# WX0_009_152DL.net
KiCad netlist of a schematic drawn in Altium Designer
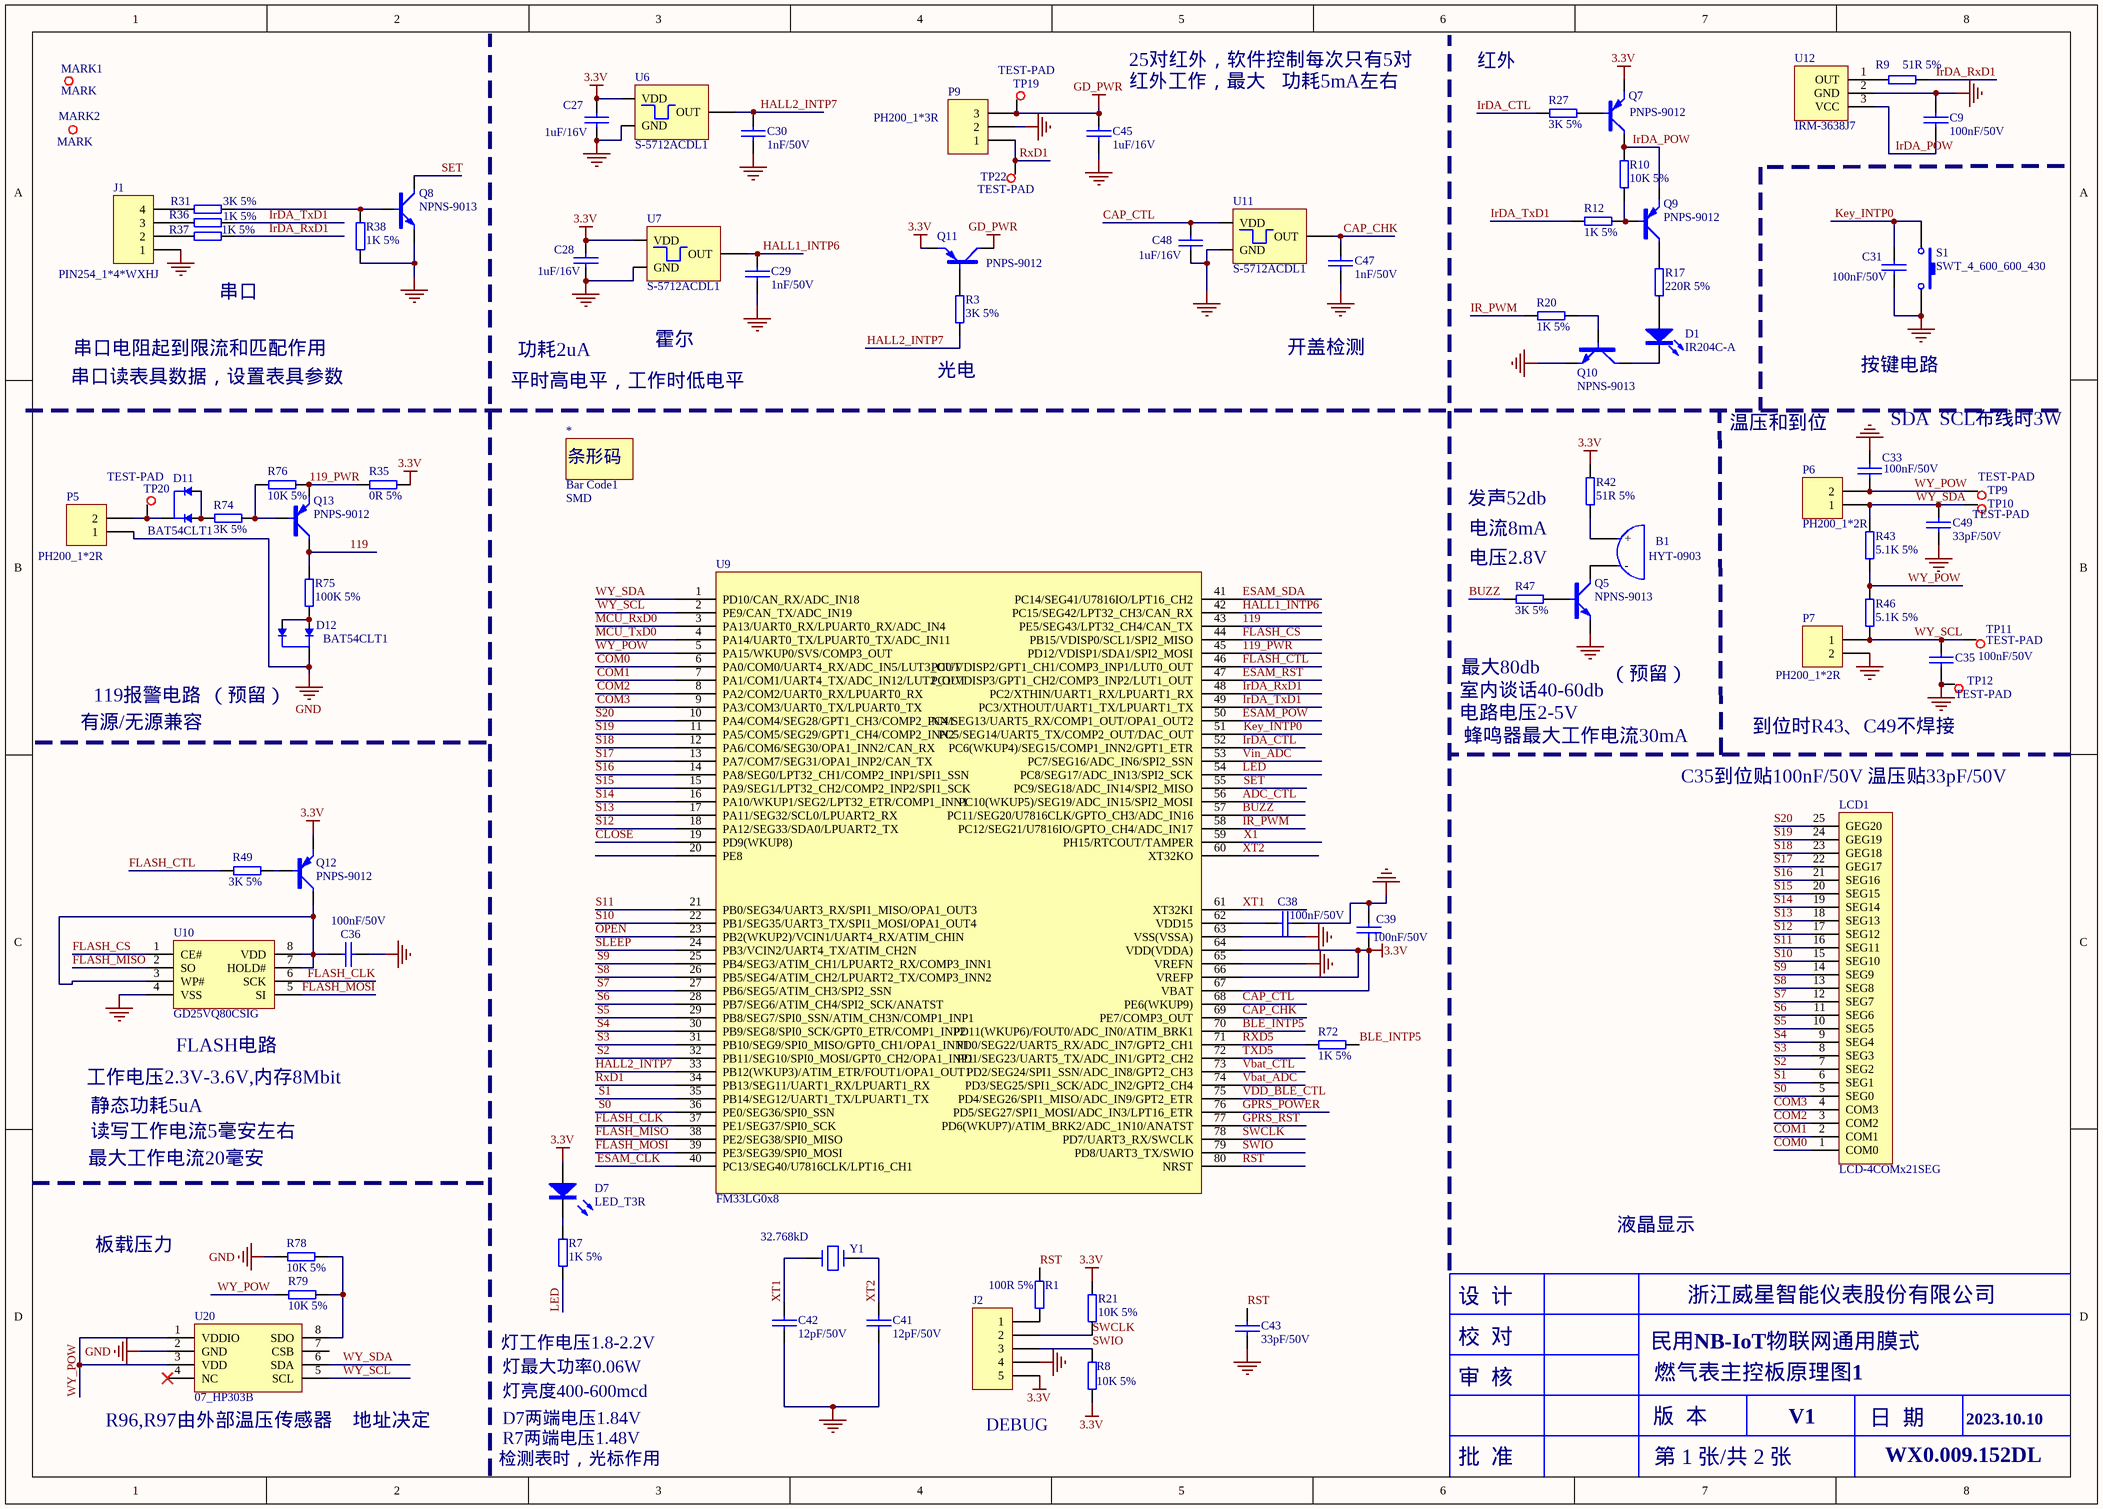
[diagram p0: WX0.009.152DL.SchDoc]

(export (version "E")
  (design (tool "Eeschema 10.0.6"))
  (components
    (comp (ref "*")
      (value "Bar Code1")
      (footprint "Bar Code1")
      (description "条形码 ,填充，无需焊接器件")
      (fields (field (name "PART NUMBER") "AD_WXHJ_Bar Code_02") (field (name "SMD/DIP") "SMD"))
      (libsource (lib "Database_Libs2") (part "05_AD_WXHJ_Bar Code_02"))
    )
    (comp (ref "B1")
      (value "HYT-0903")
      (footprint "HYT-0903")
      (description "直插,直径9mm,高5.5mm,5 V,2 V,30 mA,兴化市华宇电子有限公司,HYT-0903")
      (fields (field (name "PART NUMBER") "1010602-0007"))
      (libsource (lib "Database_Libs2") (part "07_HYT-0903"))
    )
    (comp (ref "C9")
      (value "100nF/50V")
      (footprint "CAP0603")
      (description "104pF,50 V,±10%,0603,国巨,CC0603KRX7R9BB104")
      (fields (field (name "PART NUMBER") "101020103-0021"))
      (libsource (lib "Database_Libs2") (part "CC03K7R9_100N"))
    )
    (comp (ref "C27")
      (value "1uF/16V")
      (footprint "CAP0603")
      (description "105pF,16 V,±10%,0603,国巨,CC0603KRX7R7BB105")
      (fields (field (name "PART NUMBER") "101020103-0003"))
      (libsource (lib "Database_Libs2") (part "CC03K7R7_1U"))
    )
    (comp (ref "C28")
      (value "1uF/16V")
      (footprint "CAP0603")
      (description "105pF,16 V,±10%,0603,国巨,CC0603KRX7R7BB105")
      (fields (field (name "PART NUMBER") "101020103-0003"))
      (libsource (lib "Database_Libs2") (part "CC03K7R7_1U"))
    )
    (comp (ref "C29")
      (value "1nF/50V")
      (footprint "CAP0603")
      (description "102pF,50 V,±10%,0603,国巨,CC0603KRX7R9BB102")
      (fields (field (name "PART NUMBER") "101020103-0022"))
      (libsource (lib "Database_Libs2") (part "CC03K7R9_1N"))
    )
    (comp (ref "C30")
      (value "1nF/50V")
      (footprint "CAP0603")
      (description "102pF,50 V,±10%,0603,国巨,CC0603KRX7R9BB102")
      (fields (field (name "PART NUMBER") "101020103-0022"))
      (libsource (lib "Database_Libs2") (part "CC03K7R9_1N"))
    )
    (comp (ref "C31")
      (value "100nF/50V")
      (footprint "CAP0603")
      (description "104pF,50 V,±10%,0603,国巨,CC0603KRX7R9BB104")
      (fields (field (name "PART NUMBER") "101020103-0021"))
      (libsource (lib "Database_Libs2") (part "CC03K7R9_100N"))
    )
    (comp (ref "C33")
      (value "100nF/50V")
      (footprint "CAP0603")
      (description "104pF,50 V,±10%,0603,国巨,CC0603KRX7R9BB104")
      (fields (field (name "PART NUMBER") "101020103-0021"))
      (libsource (lib "Database_Libs2") (part "CC03K7R9_100N"))
    )
    (comp (ref "C35")
      (value "100nF/50V")
      (footprint "CAP0603")
      (description "104pF,50 V,±10%,0603,国巨,CC0603KRX7R9BB104")
      (fields (field (name "PART NUMBER") "101020103-0021"))
      (libsource (lib "Database_Libs2") (part "CC03K7R9_100N"))
    )
    (comp (ref "C36")
      (value "100nF/50V")
      (footprint "CAP0603")
      (description "104pF,50 V,±10%,0603,国巨,CC0603KRX7R9BB104")
      (fields (field (name "PART NUMBER") "101020103-0021"))
      (libsource (lib "Database_Libs2") (part "CC03K7R9_100N"))
    )
    (comp (ref "C38")
      (value "100nF/50V")
      (footprint "CAP0603")
      (description "104pF,50 V,±10%,0603,国巨,CC0603KRX7R9BB104")
      (fields (field (name "PART NUMBER") "101020103-0021"))
      (libsource (lib "Database_Libs2") (part "CC03K7R9_100N"))
    )
    (comp (ref "C39")
      (value "100nF/50V")
      (footprint "CAP0603")
      (description "104pF,50 V,±10%,0603,国巨,CC0603KRX7R9BB104")
      (fields (field (name "PART NUMBER") "101020103-0021"))
      (libsource (lib "Database_Libs2") (part "CC03K7R9_100N"))
    )
    (comp (ref "C41")
      (value "12pF/50V")
      (footprint "CAP0603")
      (description "12P,50 V,±5%,0603,国巨,CC0603JRNPO9BN12")
      (fields (field (name "PART NUMBER") "101020103-0005"))
      (libsource (lib "Database_Libs2") (part "CC03JPO9_12P"))
    )
    (comp (ref "C42")
      (value "12pF/50V")
      (footprint "CAP0603")
      (description "12P,50 V,±5%,0603,国巨,CC0603JRNPO9BN12")
      (fields (field (name "PART NUMBER") "101020103-0005"))
      (libsource (lib "Database_Libs2") (part "CC03JPO9_12P"))
    )
    (comp (ref "C43")
      (value "33pF/50V")
      (footprint "CAP0603")
      (description "33pF,50 V,±10%,0603,国巨,CC0603KRNPO9BN33")
      (fields (field (name "PART NUMBER") "101020103-0027"))
      (libsource (lib "Database_Libs2") (part "CC03KPO9_33P"))
    )
    (comp (ref "C45")
      (value "1uF/16V")
      (footprint "CAP0603")
      (description "105pF,16 V,±10%,0603,国巨,CC0603KRX7R7BB105")
      (fields (field (name "PART NUMBER") "101020103-0003"))
      (libsource (lib "Database_Libs2") (part "CC03K7R7_1U"))
    )
    (comp (ref "C47")
      (value "1nF/50V")
      (footprint "CAP0603")
      (description "102pF,50 V,±10%,0603,国巨,CC0603KRX7R9BB102")
      (fields (field (name "PART NUMBER") "101020103-0022"))
      (libsource (lib "Database_Libs2") (part "CC03K7R9_1N"))
    )
    (comp (ref "C48")
      (value "1uF/16V")
      (footprint "CAP0603")
      (description "105pF,16 V,±10%,0603,国巨,CC0603KRX7R7BB105")
      (fields (field (name "PART NUMBER") "101020103-0003"))
      (libsource (lib "Database_Libs2") (part "CC03K7R7_1U"))
    )
    (comp (ref "C49")
      (value "33pF/50V")
      (footprint "CAP0603")
      (description "33pF,50 V,±10%,0603,国巨,CC0603KRNPO9BN33")
      (fields (field (name "PART NUMBER") "101020103-0027"))
      (libsource (lib "Database_Libs2") (part "CC03KPO9_33P"))
    )
    (comp (ref "D1")
      (value "IR204C-A")
      (footprint "IR_254_532_300")
      (fields (field (name "PART NUMBER") "1010502-0005"))
      (libsource (lib "Database_Libs2") (part "01_IR204C-A"))
    )
    (comp (ref "D7")
      (value "LED_T3R")
      (footprint "LED2_300")
      (description "圆形插件,3mm 圆形,插件,红光,湖北匡通电子有限公司,3BB4HC")
      (fields (field (name "PART NUMBER") "101040102-0001"))
      (libsource (lib "Database_Libs2") (part "01-LED_T3R"))
    )
    (comp (ref "D11")
      (value "BAT54CLT1")
      (footprint "SOT-23")
      (description "BAT54CLT1，SOT23-3,SOT23-3,0.2 A,0.8 V,30 V,安森美,BAT54CLT1")
      (fields (field (name "PART NUMBER") "101040101-0038"))
      (libsource (lib "Database_Libs2") (part "02_BAT54CLT1"))
    )
    (comp (ref "D12")
      (value "BAT54CLT1")
      (footprint "SOT-23")
      (description "BAT54CLT1，SOT23-3,SOT23-3,0.2 A,0.8 V,30 V,安森美,BAT54CLT1")
      (fields (field (name "PART NUMBER") "101040101-0038"))
      (libsource (lib "Database_Libs2") (part "02_BAT54CLT1"))
    )
    (comp (ref "J1")
      (value "PIN254_1*4*WXHJ")
      (footprint "PIN254_1*4*WXHJ")
      (description "1*4 ，Φ1.0 ，2.54mm，直脚,无需焊接器件")
      (fields (field (name "PART NUMBER") "AD_WXHJ_PinHeader_01"))
      (libsource (lib "Database_Libs2") (part "PIN254_1*4*WXHJ"))
    )
    (comp (ref "J2")
      (value "PIN254_1*5*WXHJ")
      (footprint "PIN254_1*5*WXHJ")
      (description "1*5 ，Φ1.0 ，2.54mm，直脚,无需焊接器件")
      (fields (field (name "PART NUMBER") "AD_WXHJ_PinHeader_02"))
      (libsource (lib "Database_Libs2") (part "PIN254_1*5*WXHJ"))
    )
    (comp (ref "LCD1")
      (value "GVH26634A-HPP")
      (footprint "PCBComponent_1")
      (description "GVH26634A-HPP-WG,65mm*23mm,针脚,段码,21,液晶,全透,70 ℃,-20 ℃,安徽金视界光电科技有限公司,GVH26634A-HPP-WG")
      (fields (field (name "PART NUMBER") "1010801-0055") (field (name "SMD/DIP") "LCD-4COMx21SEG"))
      (libsource (lib "Database_Libs2") (part "03_LCD_GVH26634A-HPP"))
    )
    (comp (ref "MARK1")
      (value "MARK")
      (footprint "MARK")
      (description "MARK点")
      (fields (field (name "PART NUMBER") "AD_WXHJ_MARK_01"))
      (libsource (lib "Database_Libs2") (part "MARK"))
    )
    (comp (ref "MARK2")
      (value "MARK")
      (footprint "MARK")
      (description "MARK点")
      (fields (field (name "PART NUMBER") "AD_WXHJ_MARK_01"))
      (libsource (lib "Database_Libs2") (part "MARK"))
    )
    (comp (ref "P5")
      (value "PH200_1*2R")
      (footprint "PH200_1*2R")
      (description "2.0-2AW,直插弯座，2PIN，脚间距2mm，带防翘起,公头,单排,2.0-2AW;直插弯座，2PIN,脚间距2mm，带防翘起")
      (fields (field (name "PART NUMBER") "1010902-0105"))
      (libsource (lib "Database_Libs2") (part "PH200_1*2R"))
    )
    (comp (ref "P6")
      (value "PH200_1*2R")
      (footprint "PCBComponent_1 - duplicate")
      (description "2.0-2AW,直插弯座，2PIN，脚间距2mm，带防翘起,公头,单排,2.0-2AW;直插弯座，2PIN,脚间距2mm，带防翘起")
      (fields (field (name "PART NUMBER") "1010902-0105"))
      (libsource (lib "Database_Libs2") (part "PH200_1*2R"))
    )
    (comp (ref "P7")
      (value "PH200_1*2R")
      (footprint "PH200_1*2R")
      (description "2.0-2AW,直插弯座，2PIN，脚间距2mm，带防翘起,公头,单排,2.0-2AW;直插弯座，2PIN,脚间距2mm，带防翘起")
      (fields (field (name "PART NUMBER") "1010902-0105"))
      (libsource (lib "") (part "PH200_1*2R_1"))
    )
    (comp (ref "P9")
      (value "PH200_1*3R")
      (footprint "PH200_1*3R")
      (description "2.0-3AW,3PIN，2mm脚间距,公头,单排,2.0-3AW；3PIN，脚间距2mm直插弯座带防翘起")
      (fields (field (name "PART NUMBER") "1010902-0104"))
      (libsource (lib "Database_Libs2") (part "PH200_1*3R"))
    )
    (comp (ref "Q5")
      (value "NPNS-9013")
      (footprint "SOT-23")
      (description "9013,NPN,SOT-23,长电,S9013")
      (fields (field (name "PART NUMBER") "101040201-0002"))
      (libsource (lib "Database_Libs2") (part "03_NPNS-9013"))
    )
    (comp (ref "Q7")
      (value "PNPS-9012")
      (footprint "SOT-23")
      (description "9012,PNP,SOT-23,JCET;长电,S9012")
      (fields (field (name "PART NUMBER") "101040201-0001"))
      (libsource (lib "Database_Libs2") (part "03_PNPS-9012"))
    )
    (comp (ref "Q8")
      (value "NPNS-9013")
      (footprint "SOT-23")
      (description "9013,NPN,SOT-23,长电,S9013")
      (fields (field (name "PART NUMBER") "101040201-0002"))
      (libsource (lib "Database_Libs2") (part "03_NPNS-9013"))
    )
    (comp (ref "Q9")
      (value "PNPS-9012")
      (footprint "SOT-23")
      (description "9012,PNP,SOT-23,JCET;长电,S9012")
      (fields (field (name "PART NUMBER") "101040201-0001"))
      (libsource (lib "Database_Libs2") (part "03_PNPS-9012"))
    )
    (comp (ref "Q10")
      (value "NPNS-9013")
      (footprint "SOT-23")
      (description "9013,NPN,SOT-23,长电,S9013")
      (fields (field (name "PART NUMBER") "101040201-0002"))
      (libsource (lib "Database_Libs2") (part "03_NPNS-9013"))
    )
    (comp (ref "Q11")
      (value "PNPS-9012")
      (footprint "SOT-23")
      (description "9012,PNP,SOT-23,JCET;长电,S9012")
      (fields (field (name "PART NUMBER") "101040201-0001"))
      (libsource (lib "Database_Libs2") (part "03_PNPS-9012"))
    )
    (comp (ref "Q12")
      (value "PNPS-9012")
      (footprint "SOT-23")
      (description "9012,PNP,SOT-23,JCET;长电,S9012")
      (fields (field (name "PART NUMBER") "101040201-0001"))
      (libsource (lib "Database_Libs2") (part "03_PNPS-9012"))
    )
    (comp (ref "Q13")
      (value "PNPS-9012")
      (footprint "SOT-23")
      (description "9012,PNP,SOT-23,JCET;长电,S9012")
      (fields (field (name "PART NUMBER") "101040201-0001"))
      (libsource (lib "Database_Libs2") (part "03_PNPS-9012"))
    )
    (comp (ref "R1")
      (value "100R 5%")
      (footprint "RES0603")
      (description "100R,±5%,1/10W,0603,国巨,RC0603JR-07100RL")
      (fields (field (name "PART NUMBER") "101010103-0022"))
      (libsource (lib "Database_Libs2") (part "RC03J_100R"))
    )
    (comp (ref "R3")
      (value "3K 5%")
      (footprint "RES0603")
      (description "国巨,±5%,0603,,155 ℃,-55 ℃,RC0603JR-073KL,无铅,100 ppm/℃,1/10W,,3K")
      (fields (field (name "PART NUMBER") "101010103-0006"))
      (libsource (lib "Database_Libs2") (part "RC03J_3K"))
    )
    (comp (ref "R7")
      (value "1K 5%")
      (footprint "RES0603")
      (description "1K,±5%,1/10W,0603,国巨,RC0603JR-071KL")
      (fields (field (name "PART NUMBER") "101010103-0008"))
      (libsource (lib "Database_Libs2") (part "RC03J_1K"))
    )
    (comp (ref "R8")
      (value "10K 5%")
      (footprint "RES0603")
      (description "国巨,±5%,0603,,155 ℃,-55 ℃,RC0603JR-0710KL,无铅,200 ppm/℃,1/10W,,10K")
      (fields (field (name "PART NUMBER") "101010103-0003"))
      (libsource (lib "Database_Libs2") (part "RC03J_10K"))
    )
    (comp (ref "R9")
      (value "51R 5%")
      (footprint "RES0603")
      (description "国巨,±5%,0603,,155 ℃,-55 ℃,RC0603JR-0751RL,无铅,100 ppm/℃,1/10W,,51欧")
      (fields (field (name "PART NUMBER") "101010103-0037"))
      (libsource (lib "Database_Libs2") (part "RC03J_51R"))
    )
    (comp (ref "R10")
      (value "10K 5%")
      (footprint "RES0603")
      (description "国巨,±5%,0603,,155 ℃,-55 ℃,RC0603JR-0710KL,无铅,200 ppm/℃,1/10W,,10K")
      (fields (field (name "PART NUMBER") "101010103-0003"))
      (libsource (lib "Database_Libs2") (part "RC03J_10K"))
    )
    (comp (ref "R12")
      (value "1K 5%")
      (footprint "RES0603")
      (description "1K,±5%,1/10W,0603,国巨,RC0603JR-071KL")
      (fields (field (name "PART NUMBER") "101010103-0008"))
      (libsource (lib "Database_Libs2") (part "RC03J_1K"))
    )
    (comp (ref "R17")
      (value "220R 5%")
      (footprint "RES0603")
      (description "220±5%,1/10W,0603,国巨,RC0603JR-07220RL")
      (fields (field (name "PART NUMBER") "101010103-0019"))
      (libsource (lib "Database_Libs2") (part "RC03J_220R"))
    )
    (comp (ref "R20")
      (value "1K 5%")
      (footprint "RES0603")
      (description "1K,±5%,1/10W,0603,国巨,RC0603JR-071KL")
      (fields (field (name "PART NUMBER") "101010103-0008"))
      (libsource (lib "Database_Libs2") (part "RC03J_1K"))
    )
    (comp (ref "R21")
      (value "10K 5%")
      (footprint "RES0603")
      (description "国巨,±5%,0603,,155 ℃,-55 ℃,RC0603JR-0710KL,无铅,200 ppm/℃,1/10W,,10K")
      (fields (field (name "PART NUMBER") "101010103-0003"))
      (libsource (lib "Database_Libs2") (part "RC03J_10K"))
    )
    (comp (ref "R27")
      (value "3K 5%")
      (footprint "RES0603")
      (description "国巨,±5%,0603,,155 ℃,-55 ℃,RC0603JR-073KL,无铅,100 ppm/℃,1/10W,,3K")
      (fields (field (name "PART NUMBER") "101010103-0006"))
      (libsource (lib "Database_Libs2") (part "RC03J_3K"))
    )
    (comp (ref "R31")
      (value "3K 5%")
      (footprint "RES0603")
      (description "国巨,±5%,0603,,155 ℃,-55 ℃,RC0603JR-073KL,无铅,100 ppm/℃,1/10W,,3K")
      (fields (field (name "PART NUMBER") "101010103-0006"))
      (libsource (lib "Database_Libs2") (part "RC03J_3K"))
    )
    (comp (ref "R35")
      (value "0R 5%")
      (footprint "RES1206")
      (description "0Ω,±5%,1/4W,1206,国巨,RC1206JR-070RL")
      (fields (field (name "PART NUMBER") "101010101-0013"))
      (libsource (lib "Database_Libs2") (part "RC06J_0R"))
    )
    (comp (ref "R36")
      (value "1K 5%")
      (footprint "RES0603")
      (description "1K,±5%,1/10W,0603,国巨,RC0603JR-071KL")
      (fields (field (name "PART NUMBER") "101010103-0008"))
      (libsource (lib "Database_Libs2") (part "RC03J_1K"))
    )
    (comp (ref "R37")
      (value "1K 5%")
      (footprint "RES0603")
      (description "1K,±5%,1/10W,0603,国巨,RC0603JR-071KL")
      (fields (field (name "PART NUMBER") "101010103-0008"))
      (libsource (lib "Database_Libs2") (part "RC03J_1K"))
    )
    (comp (ref "R38")
      (value "1K 5%")
      (footprint "RES0603")
      (description "1K,±5%,1/10W,0603,国巨,RC0603JR-071KL")
      (fields (field (name "PART NUMBER") "101010103-0008"))
      (libsource (lib "Database_Libs2") (part "RC03J_1K"))
    )
    (comp (ref "R42")
      (value "51R 5%")
      (footprint "RES0603")
      (description "国巨,±5%,0603,,155 ℃,-55 ℃,RC0603JR-0751RL,无铅,100 ppm/℃,1/10W,,51欧")
      (fields (field (name "PART NUMBER") "101010103-0037"))
      (libsource (lib "Database_Libs2") (part "RC03J_51R"))
    )
    (comp (ref "R43")
      (value "5.1K 5%")
      (footprint "RES0603")
      (description "国巨,±5%,0603,,155 ℃,55 ℃,RC0603JR-075.1KL,无铅,200 ppm/℃,1/10W,,5.1k")
      (fields (field (name "PART NUMBER") "101010103-0015"))
      (libsource (lib "Database_Libs2") (part "RC03J_5.1K"))
    )
    (comp (ref "R46")
      (value "5.1K 5%")
      (footprint "RES0603")
      (description "国巨,±5%,0603,,155 ℃,55 ℃,RC0603JR-075.1KL,无铅,200 ppm/℃,1/10W,,5.1k")
      (fields (field (name "PART NUMBER") "101010103-0015"))
      (libsource (lib "Database_Libs2") (part "RC03J_5.1K"))
    )
    (comp (ref "R47")
      (value "3K 5%")
      (footprint "RES0603")
      (description "国巨,±5%,0603,,155 ℃,-55 ℃,RC0603JR-073KL,无铅,100 ppm/℃,1/10W,,3K")
      (fields (field (name "PART NUMBER") "101010103-0006"))
      (libsource (lib "Database_Libs2") (part "RC03J_3K"))
    )
    (comp (ref "R49")
      (value "3K 5%")
      (footprint "RES0603")
      (description "国巨,±5%,0603,,155 ℃,-55 ℃,RC0603JR-073KL,无铅,100 ppm/℃,1/10W,,3K")
      (fields (field (name "PART NUMBER") "101010103-0006"))
      (libsource (lib "Database_Libs2") (part "RC03J_3K"))
    )
    (comp (ref "R72")
      (value "1K 5%")
      (footprint "RES0603")
      (description "1K,±5%,1/10W,0603,国巨,RC0603JR-071KL")
      (fields (field (name "PART NUMBER") "101010103-0008"))
      (libsource (lib "Database_Libs2") (part "RC03J_1K"))
    )
    (comp (ref "R74")
      (value "3K 5%")
      (footprint "RES0603")
      (description "国巨,±5%,0603,,155 ℃,-55 ℃,RC0603JR-073KL,无铅,100 ppm/℃,1/10W,,3K")
      (fields (field (name "PART NUMBER") "101010103-0006"))
      (libsource (lib "Database_Libs2") (part "RC03J_3K"))
    )
    (comp (ref "R75")
      (value "100K 5%")
      (footprint "RES0603")
      (description "国巨,±5%,0603,,155 ℃,-55 ℃,RC0603JR-07100KL,无铅,100 ppm/℃,1/10W,,100K")
      (fields (field (name "PART NUMBER") "101010103-0005"))
      (libsource (lib "Database_Libs2") (part "RC03J_100K"))
    )
    (comp (ref "R76")
      (value "10K 5%")
      (footprint "RES0603")
      (description "国巨,±5%,0603,,155 ℃,-55 ℃,RC0603JR-0710KL,无铅,200 ppm/℃,1/10W,,10K")
      (fields (field (name "PART NUMBER") "101010103-0003"))
      (libsource (lib "Database_Libs2") (part "RC03J_10K"))
    )
    (comp (ref "R78")
      (value "10K 5%")
      (footprint "RES0603")
      (description "国巨,±5%,0603,,155 ℃,-55 ℃,RC0603JR-071ML,无铅,200 ppm/℃,1/10W,,1M")
      (fields (field (name "PART NUMBER") "101010103-0002"))
      (libsource (lib "Database_Libs2") (part "RC03J_1M"))
    )
    (comp (ref "R79")
      (value "10K 5%")
      (footprint "RES0603")
      (description "国巨,±5%,0603,,155 ℃,-55 ℃,RC0603JR-071ML,无铅,200 ppm/℃,1/10W,,1M")
      (fields (field (name "PART NUMBER") "101010103-0002"))
      (libsource (lib "Database_Libs2") (part "RC03J_1M"))
    )
    (comp (ref "S1")
      (value "SWT_4_600_600_430")
      (footprint "SWT_4_600_600")
      (description "TS-1102,机械轻触,6*6*4.3直插,6*6*4.3直插,乐清市羽欧电子")
      (fields (field (name "PART NUMBER") "1011001-0027"))
      (libsource (lib "Database_Libs2") (part "07_SWT_4_600_600_430"))
    )
    (comp (ref "TP9")
      (value "TEST-PAD")
      (footprint "TEST-PAD")
      (description "单面焊盘测试点")
      (fields (field (name "PART NUMBER") "AD_WXHJ_TEST-PAD_01"))
      (libsource (lib "Database_Libs2") (part "TEST-PAD"))
    )
    (comp (ref "TP10")
      (value "TEST-PAD")
      (footprint "TEST-PAD")
      (description "单面焊盘测试点")
      (fields (field (name "PART NUMBER") "AD_WXHJ_TEST-PAD_01"))
      (libsource (lib "Database_Libs2") (part "TEST-PAD"))
    )
    (comp (ref "TP11")
      (value "TEST-PAD")
      (footprint "TEST-PAD")
      (description "单面焊盘测试点")
      (fields (field (name "PART NUMBER") "AD_WXHJ_TEST-PAD_01"))
      (libsource (lib "Database_Libs2") (part "TEST-PAD"))
    )
    (comp (ref "TP12")
      (value "TEST-PAD")
      (footprint "TEST-PAD")
      (description "单面焊盘测试点")
      (fields (field (name "PART NUMBER") "AD_WXHJ_TEST-PAD_01"))
      (libsource (lib "Database_Libs2") (part "TEST-PAD"))
    )
    (comp (ref "TP19")
      (value "TEST-PAD")
      (footprint "TEST-PAD")
      (description "单面焊盘测试点")
      (fields (field (name "PART NUMBER") "AD_WXHJ_TEST-PAD_01"))
      (libsource (lib "Database_Libs2") (part "TEST-PAD"))
    )
    (comp (ref "TP20")
      (value "TEST-PAD")
      (footprint "TEST-PAD")
      (description "单面焊盘测试点")
      (fields (field (name "PART NUMBER") "AD_WXHJ_TEST-PAD_01"))
      (libsource (lib "Database_Libs2") (part "TEST-PAD"))
    )
    (comp (ref "TP22")
      (value "TEST-PAD")
      (footprint "TEST-PAD")
      (description "单面焊盘测试点")
      (fields (field (name "PART NUMBER") "AD_WXHJ_TEST-PAD_01"))
      (libsource (lib "Database_Libs2") (part "TEST-PAD"))
    )
    (comp (ref "U6")
      (value "S-5712ACDL1")
      (footprint "SOT-23")
      (description "S-5712ACDL1,SOT23-3,3.5 V,1.6 V,2 uA,精工电子,S-5712ACDL1")
      (fields (field (name "PART NUMBER") "1010504-0002"))
      (libsource (lib "Database_Libs2") (part "01_S-5712ACDL1"))
    )
    (comp (ref "U7")
      (value "S-5712ACDL1")
      (footprint "SOT-23")
      (description "S-5712ACDL1,SOT23-3,3.5 V,1.6 V,2 uA,精工电子,S-5712ACDL1")
      (fields (field (name "PART NUMBER") "1010504-0002"))
      (libsource (lib "Database_Libs2") (part "01_S-5712ACDL1"))
    )
    (comp (ref "U9") (value "FM33LG0x8") (footprint "LQFP80") (libsource (lib "FM_MCU") (part "FM33LG0x8")))
    (comp (ref "U10")
      (value "GD25VQ80CSIG")
      (footprint "SOP-8L-200MIL")
      (description "GD25VQ80CSIG,SOP8 208mil,北京兆易创新科技股份有限公司,GD25VQ80CSIG")
      (fields (field (name "PART NUMBER") "101050101-0165"))
      (libsource (lib "Database_Libs2") (part "04_GD25VQ80CSIG"))
    )
    (comp (ref "U11")
      (value "S-5712ACDL1")
      (footprint "SOT-23")
      (description "S-5712ACDL1,SOT23-3,3.5 V,1.6 V,2 uA,精工电子,S-5712ACDL1")
      (fields (field (name "PART NUMBER") "1010504-0002"))
      (libsource (lib "Database_Libs2") (part "01_S-5712ACDL1"))
    )
    (comp (ref "U12")
      (value "IRM-3638J7")
      (footprint "IRM-3638J7")
      (description "IRM-3638J7  直脚,插件,6 V,6 V,亿光电子工业股份有限公司,IRM-3638J7")
      (fields (field (name "PART NUMBER") "101040101-0059"))
      (libsource (lib "Database_Libs2") (part "01_IRM-3638J7"))
    )
    (comp (ref "U20")
      (value "07_HP303B")
      (footprint "HP303B")
      (description "HP303B,4.7mm*3.7mm,惠贻华普,HP303B,含铅")
      (fields (field (name "PART NUMBER") "1011301-0022"))
      (libsource (lib "Database_Libs2") (part "07_HP303B"))
    )
    (comp (ref "Y1")
      (value "32.768kD")
      (footprint "SMD-3215_2P")
      (fields (field (name "PART NUMBER") "1010601-0020"))
      (libsource (lib "Database_Libs2") (part "04_XTALSG12MD_32.768kD"))
    )
  )
  (nets
    (net (code "1") (name "/119") (class "Default")
      (node (ref "Q13") (pin "3") (pinfunction "C_3") (pintype "passive"))
      (node (ref "R75") (pin "2") (pinfunction "2_2") (pintype "passive"))
      (node (ref "U9") (pin "43") (pinfunction "PE5/SEG43/LPT32_CH4/CAN_TX_43") (pintype "passive"))
    )
    (net (code "2") (name "/119_PWR") (class "Default")
      (node (ref "Q13") (pin "2") (pinfunction "E_2") (pintype "passive"))
      (node (ref "R35") (pin "2") (pinfunction "2_2") (pintype "passive"))
      (node (ref "R76") (pin "1") (pinfunction "1_1") (pintype "passive"))
      (node (ref "U9") (pin "45") (pinfunction "PD12/VDISP1/SDA1/SPI2_MOSI_45") (pintype "passive"))
    )
    (net (code "3") (name "/ADC_CTL") (class "Default")
      (node (ref "U9") (pin "56") (pinfunction "PC10(WKUP5)/SEG19/ADC_IN15/SPI2_MOSI_56") (pintype "passive"))
    )
    (net (code "4") (name "/BLE_INTP5") (class "Default")
      (node (ref "R72") (pin "1") (pinfunction "1_1") (pintype "passive"))
      (node (ref "U9") (pin "70") (pinfunction "PD11(WKUP6)/FOUT0/ADC_IN0/ATIM_BRK1_70") (pintype "passive"))
    )
    (net (code "5") (name "/BUZZ") (class "Default")
      (node (ref "R47") (pin "1") (pinfunction "1_1") (pintype "passive"))
      (node (ref "U9") (pin "57") (pinfunction "PC11/SEG20/U7816CLK/GPTO_CH3/ADC_IN16_57") (pintype "passive"))
    )
    (net (code "6") (name "/CAP_CHK") (class "Default")
      (node (ref "C47") (pin "1") (pinfunction "1_1") (pintype "passive"))
      (node (ref "U11") (pin "2") (pinfunction "OUT_2") (pintype "passive"))
      (node (ref "U9") (pin "69") (pinfunction "PE7/COMP3_OUT_69") (pintype "passive"))
    )
    (net (code "7") (name "/CAP_CTL") (class "Default")
      (node (ref "C48") (pin "1") (pinfunction "1_1") (pintype "passive"))
      (node (ref "U11") (pin "1") (pinfunction "VDD_1") (pintype "passive"))
      (node (ref "U9") (pin "68") (pinfunction "PE6(WKUP9)_68") (pintype "passive"))
    )
    (net (code "8") (name "/CLOSE") (class "Default")
      (node (ref "U9") (pin "19") (pinfunction "PD9(WKUP8)_19") (pintype "passive"))
    )
    (net (code "9") (name "/COM0") (class "Default")
      (node (ref "LCD1") (pin "1") (pinfunction "COM0_1") (pintype "passive"))
      (node (ref "U9") (pin "6") (pinfunction "PA0/COM0/UART4_RX/ADC_IN5/LUT3_OUT_6") (pintype "passive"))
    )
    (net (code "10") (name "/COM1") (class "Default")
      (node (ref "LCD1") (pin "2") (pinfunction "COM1_2") (pintype "passive"))
      (node (ref "U9") (pin "7") (pinfunction "PA1/COM1/UART4_TX/ADC_IN12/LUT2_OUT_7") (pintype "passive"))
    )
    (net (code "11") (name "/COM2") (class "Default")
      (node (ref "LCD1") (pin "3") (pinfunction "COM2_3") (pintype "passive"))
      (node (ref "U9") (pin "8") (pinfunction "PA2/COM2/UART0_RX/LPUART0_RX_8") (pintype "passive"))
    )
    (net (code "12") (name "/COM3") (class "Default")
      (node (ref "LCD1") (pin "4") (pinfunction "COM3_4") (pintype "passive"))
      (node (ref "U9") (pin "9") (pinfunction "PA3/COM3/UART0_TX/LPUART0_TX_9") (pintype "passive"))
    )
    (net (code "13") (name "/ESAM_CLK") (class "Default")
      (node (ref "U9") (pin "40") (pinfunction "PC13/SEG40/U7816CLK/LPT16_CH1_40") (pintype "passive"))
    )
    (net (code "14") (name "/ESAM_POW") (class "Default")
      (node (ref "U9") (pin "50") (pinfunction "PC4/SEG13/UART5_RX/COMP1_OUT/OPA1_OUT2_50") (pintype "passive"))
    )
    (net (code "15") (name "/ESAM_RST") (class "Default")
      (node (ref "U9") (pin "47") (pinfunction "PC1/VDISP3/GPT1_CH2/COMP3_INP2/LUT1_OUT_47") (pintype "passive"))
    )
    (net (code "16") (name "/ESAM_SDA") (class "Default")
      (node (ref "U9") (pin "41") (pinfunction "PC14/SEG41/U7816IO/LPT16_CH2_41") (pintype "passive"))
    )
    (net (code "17") (name "/FLASH_CLK") (class "Default")
      (node (ref "U10") (pin "6") (pinfunction "SCK_6") (pintype "passive"))
      (node (ref "U9") (pin "37") (pinfunction "PE1/SEG37/SPI0_SCK_37") (pintype "passive"))
    )
    (net (code "18") (name "/FLASH_CS") (class "Default")
      (node (ref "U10") (pin "1") (pinfunction "CE#_1") (pintype "passive"))
      (node (ref "U9") (pin "44") (pinfunction "PB15/VDISP0/SCL1/SPI2_MISO_44") (pintype "passive"))
    )
    (net (code "19") (name "/FLASH_CTL") (class "Default")
      (node (ref "R49") (pin "1") (pinfunction "1_1") (pintype "passive"))
      (node (ref "U9") (pin "46") (pinfunction "PC0/VDISP2/GPT1_CH1/COMP3_INP1/LUT0_OUT_46") (pintype "passive"))
    )
    (net (code "20") (name "/FLASH_MISO") (class "Default")
      (node (ref "U10") (pin "2") (pinfunction "SO_2") (pintype "passive"))
      (node (ref "U9") (pin "38") (pinfunction "PE2/SEG38/SPI0_MISO_38") (pintype "passive"))
    )
    (net (code "21") (name "/FLASH_MOSI") (class "Default")
      (node (ref "U10") (pin "5") (pinfunction "SI_5") (pintype "passive"))
      (node (ref "U9") (pin "39") (pinfunction "PE3/SEG39/SPI0_MOSI_39") (pintype "passive"))
    )
    (net (code "22") (name "/GPRS_POWER") (class "Default")
      (node (ref "U9") (pin "76") (pinfunction "PD5/SEG27/SPI1_MOSI/ADC_IN3/LPT16_ETR_76") (pintype "passive"))
    )
    (net (code "23") (name "/GPRS_RST") (class "Default")
      (node (ref "U9") (pin "77") (pinfunction "PD6(WKUP7)/ATIM_BRK2/ADC_1N10/ANATST_77") (pintype "passive"))
    )
    (net (code "24") (name "/HALL1_INTP6") (class "Default")
      (node (ref "C29") (pin "1") (pinfunction "1_1") (pintype "passive"))
      (node (ref "U7") (pin "2") (pinfunction "OUT_2") (pintype "passive"))
      (node (ref "U9") (pin "42") (pinfunction "PC15/SEG42/LPT32_CH3/CAN_RX_42") (pintype "passive"))
    )
    (net (code "25") (name "/HALL2_INTP7") (class "Default")
      (node (ref "C30") (pin "1") (pinfunction "1_1") (pintype "passive"))
      (node (ref "R3") (pin "1") (pinfunction "1_1") (pintype "passive"))
      (node (ref "U6") (pin "2") (pinfunction "OUT_2") (pintype "passive"))
      (node (ref "U9") (pin "33") (pinfunction "PB12(WKUP3)/ATIM_ETR/FOUT1/OPA1_OUT1_33") (pintype "passive"))
    )
    (net (code "26") (name "/IR_PWM") (class "Default")
      (node (ref "R20") (pin "1") (pinfunction "1_1") (pintype "passive"))
      (node (ref "U9") (pin "58") (pinfunction "PC12/SEG21/U7816IO/GPTO_CH4/ADC_IN17_58") (pintype "passive"))
    )
    (net (code "27") (name "/IrDA_CTL") (class "Default")
      (node (ref "R27") (pin "1") (pinfunction "1_1") (pintype "passive"))
      (node (ref "U9") (pin "52") (pinfunction "PC6(WKUP4)/SEG15/COMP1_INN2/GPT1_ETR_52") (pintype "passive"))
    )
    (net (code "28") (name "/IrDA_POW") (class "Default")
      (node (ref "C9") (pin "2") (pinfunction "2_2") (pintype "passive"))
      (node (ref "Q7") (pin "3") (pinfunction "C_3") (pintype "passive"))
      (node (ref "Q9") (pin "2") (pinfunction "E_2") (pintype "passive"))
      (node (ref "R10") (pin "2") (pinfunction "2_2") (pintype "passive"))
      (node (ref "U12") (pin "3") (pinfunction "VCC_3") (pintype "passive"))
    )
    (net (code "29") (name "/IrDA_RxD1") (class "Default")
      (node (ref "R37") (pin "2") (pinfunction "2_2") (pintype "passive"))
      (node (ref "R9") (pin "2") (pinfunction "2_2") (pintype "passive"))
      (node (ref "U9") (pin "48") (pinfunction "PC2/XTHIN/UART1_RX/LPUART1_RX_48") (pintype "passive"))
    )
    (net (code "30") (name "/IrDA_TxD1") (class "Default")
      (node (ref "R12") (pin "1") (pinfunction "1_1") (pintype "passive"))
      (node (ref "R36") (pin "2") (pinfunction "2_2") (pintype "passive"))
      (node (ref "U9") (pin "49") (pinfunction "PC3/XTHOUT/UART1_TX/LPUART1_TX_49") (pintype "passive"))
    )
    (net (code "31") (name "/Key_INTP0") (class "Default")
      (node (ref "C31") (pin "1") (pinfunction "1_1") (pintype "passive"))
      (node (ref "S1") (pin "1") (pinfunction "1_1") (pintype "passive"))
      (node (ref "U9") (pin "51") (pinfunction "PC5/SEG14/UART5_TX/COMP2_OUT/DAC_OUT_51") (pintype "passive"))
    )
    (net (code "32") (name "/LED") (class "Default")
      (node (ref "R7") (pin "1") (pinfunction "1_1") (pintype "passive"))
      (node (ref "U9") (pin "54") (pinfunction "PC8/SEG17/ADC_IN13/SPI2_SCK_54") (pintype "passive"))
    )
    (net (code "33") (name "/MCU_RxD0") (class "Default")
      (node (ref "U9") (pin "3") (pinfunction "PA13/UART0_RX/LPUART0_RX/ADC_IN4_3") (pintype "passive"))
    )
    (net (code "34") (name "/MCU_TxD0") (class "Default")
      (node (ref "U9") (pin "4") (pinfunction "PA14/UART0_TX/LPUART0_TX/ADC_IN11_4") (pintype "passive"))
    )
    (net (code "35") (name "/OPEN") (class "Default")
      (node (ref "U9") (pin "23") (pinfunction "PB2(WKUP2)/VCIN1/UART4_RX/ATIM_CHIN_23") (pintype "passive"))
    )
    (net (code "36") (name "/RST") (class "Default")
      (node (ref "C43") (pin "1") (pinfunction "1_1") (pintype "passive"))
      (node (ref "R1") (pin "1") (pinfunction "1_1") (pintype "passive"))
      (node (ref "U9") (pin "80") (pinfunction "NRST_80") (pintype "passive"))
    )
    (net (code "37") (name "/RXD5") (class "Default")
      (node (ref "R72") (pin "2") (pinfunction "2_2") (pintype "passive"))
      (node (ref "U9") (pin "71") (pinfunction "PD0/SEG22/UART5_RX/ADC_IN7/GPT2_CH1_71") (pintype "passive"))
    )
    (net (code "38") (name "/RxD1") (class "Default")
      (node (ref "P9") (pin "1") (pinfunction "1_1") (pintype "passive"))
      (node (ref "TP22") (pin "1") (pinfunction "1_1") (pintype "passive"))
      (node (ref "U9") (pin "34") (pinfunction "PB13/SEG11/UART1_RX/LPUART1_RX_34") (pintype "passive"))
    )
    (net (code "39") (name "/S0") (class "Default")
      (node (ref "LCD1") (pin "5") (pinfunction "SEG0_5") (pintype "passive"))
      (node (ref "U9") (pin "36") (pinfunction "PE0/SEG36/SPI0_SSN_36") (pintype "passive"))
    )
    (net (code "40") (name "/S1") (class "Default")
      (node (ref "LCD1") (pin "6") (pinfunction "SEG1_6") (pintype "passive"))
      (node (ref "U9") (pin "35") (pinfunction "PB14/SEG12/UART1_TX/LPUART1_TX_35") (pintype "passive"))
    )
    (net (code "41") (name "/S2") (class "Default")
      (node (ref "LCD1") (pin "7") (pinfunction "SEG2_7") (pintype "passive"))
      (node (ref "U9") (pin "32") (pinfunction "PB11/SEG10/SPI0_MOSI/GPT0_CH2/OPA1_INP1_32") (pintype "passive"))
    )
    (net (code "42") (name "/S3") (class "Default")
      (node (ref "LCD1") (pin "8") (pinfunction "SEG3_8") (pintype "passive"))
      (node (ref "U9") (pin "31") (pinfunction "PB10/SEG9/SPI0_MISO/GPT0_CH1/OPA1_INN1_31") (pintype "passive"))
    )
    (net (code "43") (name "/S4") (class "Default")
      (node (ref "LCD1") (pin "9") (pinfunction "SEG4_9") (pintype "passive"))
      (node (ref "U9") (pin "30") (pinfunction "PB9/SEG8/SPI0_SCK/GPT0_ETR/COMP1_INP2_30") (pintype "passive"))
    )
    (net (code "44") (name "/S5") (class "Default")
      (node (ref "LCD1") (pin "10") (pinfunction "SEG5_10") (pintype "passive"))
      (node (ref "U9") (pin "29") (pinfunction "PB8/SEG7/SPI0_SSN/ATIM_CH3N/COMP1_INP1_29") (pintype "passive"))
    )
    (net (code "45") (name "/S6") (class "Default")
      (node (ref "LCD1") (pin "11") (pinfunction "SEG6_11") (pintype "passive"))
      (node (ref "U9") (pin "28") (pinfunction "PB7/SEG6/ATIM_CH4/SPI2_SCK/ANATST_28") (pintype "passive"))
    )
    (net (code "46") (name "/S7") (class "Default")
      (node (ref "LCD1") (pin "12") (pinfunction "SEG7_12") (pintype "passive"))
      (node (ref "U9") (pin "27") (pinfunction "PB6/SEG5/ATIM_CH3/SPI2_SSN_27") (pintype "passive"))
    )
    (net (code "47") (name "/S8") (class "Default")
      (node (ref "LCD1") (pin "13") (pinfunction "SEG8_13") (pintype "passive"))
      (node (ref "U9") (pin "26") (pinfunction "PB5/SEG4/ATIM_CH2/LPUART2_TX/COMP3_INN2_26") (pintype "passive"))
    )
    (net (code "48") (name "/S9") (class "Default")
      (node (ref "LCD1") (pin "14") (pinfunction "SEG9_14") (pintype "passive"))
      (node (ref "U9") (pin "25") (pinfunction "PB4/SEG3/ATIM_CH1/LPUART2_RX/COMP3_INN1_25") (pintype "passive"))
    )
    (net (code "49") (name "/S10") (class "Default")
      (node (ref "LCD1") (pin "15") (pinfunction "SEG10_15") (pintype "passive"))
      (node (ref "U9") (pin "22") (pinfunction "PB1/SEG35/UART3_TX/SPI1_MOSI/OPA1_OUT4_22") (pintype "passive"))
    )
    (net (code "50") (name "/S11") (class "Default")
      (node (ref "LCD1") (pin "16") (pinfunction "SEG11_16") (pintype "passive"))
      (node (ref "U9") (pin "21") (pinfunction "PB0/SEG34/UART3_RX/SPI1_MISO/OPA1_OUT3_21") (pintype "passive"))
    )
    (net (code "51") (name "/S12") (class "Default")
      (node (ref "LCD1") (pin "17") (pinfunction "SEG12_17") (pintype "passive"))
      (node (ref "U9") (pin "18") (pinfunction "PA12/SEG33/SDA0/LPUART2_TX_18") (pintype "passive"))
    )
    (net (code "52") (name "/S13") (class "Default")
      (node (ref "LCD1") (pin "18") (pinfunction "SEG13_18") (pintype "passive"))
      (node (ref "U9") (pin "17") (pinfunction "PA11/SEG32/SCL0/LPUART2_RX_17") (pintype "passive"))
    )
    (net (code "53") (name "/S14") (class "Default")
      (node (ref "LCD1") (pin "19") (pinfunction "SEG14_19") (pintype "passive"))
      (node (ref "U9") (pin "16") (pinfunction "PA10/WKUP1/SEG2/LPT32_ETR/COMP1_INN1_16") (pintype "passive"))
    )
    (net (code "54") (name "/S15") (class "Default")
      (node (ref "LCD1") (pin "20") (pinfunction "SEG15_20") (pintype "passive"))
      (node (ref "U9") (pin "15") (pinfunction "PA9/SEG1/LPT32_CH2/COMP2_INP2/SPI1_SCK_15") (pintype "passive"))
    )
    (net (code "55") (name "/S16") (class "Default")
      (node (ref "LCD1") (pin "21") (pinfunction "SEG16_21") (pintype "passive"))
      (node (ref "U9") (pin "14") (pinfunction "PA8/SEG0/LPT32_CH1/COMP2_INP1/SPI1_SSN_14") (pintype "passive"))
    )
    (net (code "56") (name "/S17") (class "Default")
      (node (ref "LCD1") (pin "22") (pinfunction "GEG17_22") (pintype "passive"))
      (node (ref "U9") (pin "13") (pinfunction "PA7/COM7/SEG31/OPA1_INP2/CAN_TX_13") (pintype "passive"))
    )
    (net (code "57") (name "/S18") (class "Default")
      (node (ref "LCD1") (pin "23") (pinfunction "GEG18_23") (pintype "passive"))
      (node (ref "U9") (pin "12") (pinfunction "PA6/COM6/SEG30/OPA1_INN2/CAN_RX_12") (pintype "passive"))
    )
    (net (code "58") (name "/S19") (class "Default")
      (node (ref "LCD1") (pin "24") (pinfunction "GEG19_24") (pintype "passive"))
      (node (ref "U9") (pin "11") (pinfunction "PA5/COM5/SEG29/GPT1_CH4/COMP2_INN2_11") (pintype "passive"))
    )
    (net (code "59") (name "/S20") (class "Default")
      (node (ref "LCD1") (pin "25") (pinfunction "GEG20_25") (pintype "passive"))
      (node (ref "U9") (pin "10") (pinfunction "PA4/COM4/SEG28/GPT1_CH3/COMP2_INN1_10") (pintype "passive"))
    )
    (net (code "60") (name "/SET") (class "Default")
      (node (ref "Q8") (pin "3") (pinfunction "C_3") (pintype "passive"))
      (node (ref "U9") (pin "55") (pinfunction "PC9/SEG18/ADC_IN14/SPI2_MISO_55") (pintype "passive"))
    )
    (net (code "61") (name "/SLEEP") (class "Default")
      (node (ref "U9") (pin "24") (pinfunction "PB3/VCIN2/UART4_TX/ATIM_CH2N_24") (pintype "passive"))
    )
    (net (code "62") (name "/SWCLK") (class "Default")
      (node (ref "J2") (pin "2") (pinfunction "2_2") (pintype "passive"))
      (node (ref "R21") (pin "2") (pinfunction "2_2") (pintype "passive"))
      (node (ref "U9") (pin "78") (pinfunction "PD7/UART3_RX/SWCLK_78") (pintype "passive"))
    )
    (net (code "63") (name "/SWIO") (class "Default")
      (node (ref "J2") (pin "3") (pinfunction "3_3") (pintype "passive"))
      (node (ref "R8") (pin "2") (pinfunction "2_2") (pintype "passive"))
      (node (ref "U9") (pin "79") (pinfunction "PD8/UART3_TX/SWIO_79") (pintype "passive"))
    )
    (net (code "64") (name "/TXD5") (class "Default")
      (node (ref "U9") (pin "72") (pinfunction "PD1/SEG23/UART5_TX/ADC_IN1/GPT2_CH2_72") (pintype "passive"))
    )
    (net (code "65") (name "/VDD_BLE_CTL") (class "Default")
      (node (ref "U9") (pin "75") (pinfunction "PD4/SEG26/SPI1_MISO/ADC_IN9/GPT2_ETR_75") (pintype "passive"))
    )
    (net (code "66") (name "/Vbat_ADC") (class "Default")
      (node (ref "U9") (pin "74") (pinfunction "PD3/SEG25/SPI1_SCK/ADC_IN2/GPT2_CH4_74") (pintype "passive"))
    )
    (net (code "67") (name "/Vbat_CTL") (class "Default")
      (node (ref "U9") (pin "73") (pinfunction "PD2/SEG24/SPI1_SSN/ADC_IN8/GPT2_CH3_73") (pintype "passive"))
    )
    (net (code "68") (name "/Vin_ADC") (class "Default")
      (node (ref "U9") (pin "53") (pinfunction "PC7/SEG16/ADC_IN6/SPI2_SSN_53") (pintype "passive"))
    )
    (net (code "69") (name "/WY_POW") (class "Default")
      (node (ref "C33") (pin "2") (pinfunction "2_2") (pintype "passive"))
      (node (ref "P6") (pin "2") (pinfunction "2_2") (pintype "passive"))
      (node (ref "R43") (pin "1") (pinfunction "1_1") (pintype "passive"))
      (node (ref "R46") (pin "2") (pinfunction "2_2") (pintype "passive"))
      (node (ref "R79") (pin "2") (pinfunction "2_2") (pintype "passive"))
      (node (ref "TP9") (pin "1") (pinfunction "1_1") (pintype "passive"))
      (node (ref "U20") (pin "1") (pinfunction "VDDIO_1") (pintype "passive"))
      (node (ref "U20") (pin "3") (pinfunction "VDD_3") (pintype "passive"))
      (node (ref "U9") (pin "5") (pinfunction "PA15/WKUP0/SVS/COMP3_OUT_5") (pintype "passive"))
    )
    (net (code "70") (name "/WY_SCL") (class "Default")
      (node (ref "C35") (pin "1") (pinfunction "1_1") (pintype "passive"))
      (node (ref "P7") (pin "1") (pinfunction "1_1") (pintype "passive"))
      (node (ref "R46") (pin "1") (pinfunction "1_1") (pintype "passive"))
      (node (ref "TP11") (pin "1") (pinfunction "1_1") (pintype "passive"))
      (node (ref "U20") (pin "5") (pinfunction "SCL_5") (pintype "passive"))
      (node (ref "U9") (pin "2") (pinfunction "PE9/CAN_TX/ADC_IN19_2") (pintype "passive"))
    )
    (net (code "71") (name "/WY_SDA") (class "Default")
      (node (ref "C49") (pin "1") (pinfunction "1_1") (pintype "passive"))
      (node (ref "P6") (pin "1") (pinfunction "1_1") (pintype "passive"))
      (node (ref "R43") (pin "2") (pinfunction "2_2") (pintype "passive"))
      (node (ref "TP10") (pin "1") (pinfunction "1_1") (pintype "passive"))
      (node (ref "U20") (pin "6") (pinfunction "SDA_6") (pintype "passive"))
      (node (ref "U9") (pin "1") (pinfunction "PD10/CAN_RX/ADC_IN18_1") (pintype "passive"))
    )
    (net (code "72") (name "/X1") (class "Default")
      (node (ref "U9") (pin "59") (pinfunction "PH15/RTCOUT/TAMPER_59") (pintype "passive"))
    )
    (net (code "73") (name "/XT1") (class "Default")
      (node (ref "C42") (pin "1") (pinfunction "1_1") (pintype "passive"))
      (node (ref "U9") (pin "61") (pinfunction "XT32KI_61") (pintype "passive"))
      (node (ref "Y1") (pin "1") (pinfunction "1_1") (pintype "passive"))
    )
    (net (code "74") (name "/XT2") (class "Default")
      (node (ref "C41") (pin "2") (pinfunction "2_2") (pintype "passive"))
      (node (ref "U9") (pin "60") (pinfunction "XT32KO_60") (pintype "passive"))
      (node (ref "Y1") (pin "2") (pinfunction "2_2") (pintype "passive"))
    )
    (net (code "75") (name "3.3V") (class "Default")
      (node (ref "C27") (pin "1") (pinfunction "1_1") (pintype "passive"))
      (node (ref "C28") (pin "1") (pinfunction "1_1") (pintype "passive"))
      (node (ref "C39") (pin "2") (pinfunction "2_2") (pintype "passive"))
      (node (ref "D7") (pin "1") (pinfunction "1_1") (pintype "passive"))
      (node (ref "J2") (pin "5") (pinfunction "5_5") (pintype "passive"))
      (node (ref "Q11") (pin "2") (pinfunction "E_2") (pintype "passive"))
      (node (ref "Q12") (pin "2") (pinfunction "E_2") (pintype "passive"))
      (node (ref "Q7") (pin "2") (pinfunction "E_2") (pintype "passive"))
      (node (ref "R21") (pin "1") (pinfunction "1_1") (pintype "passive"))
      (node (ref "R35") (pin "1") (pinfunction "1_1") (pintype "passive"))
      (node (ref "R42") (pin "2") (pinfunction "2_2") (pintype "passive"))
      (node (ref "R8") (pin "1") (pinfunction "1_1") (pintype "passive"))
      (node (ref "U6") (pin "1") (pinfunction "VDD_1") (pintype "passive"))
      (node (ref "U7") (pin "1") (pinfunction "VDD_1") (pintype "passive"))
      (node (ref "U9") (pin "64") (pinfunction "VDD(VDDA)_64") (pintype "passive"))
      (node (ref "U9") (pin "66") (pinfunction "VREFP_66") (pintype "passive"))
      (node (ref "U9") (pin "67") (pinfunction "VBAT_67") (pintype "passive"))
    )
    (net (code "76") (name "GD_PWR") (class "Default")
      (node (ref "C45") (pin "1") (pinfunction "1_1") (pintype "passive"))
      (node (ref "P9") (pin "3") (pinfunction "3_3") (pintype "passive"))
      (node (ref "Q11") (pin "3") (pinfunction "C_3") (pintype "passive"))
      (node (ref "TP19") (pin "1") (pinfunction "1_1") (pintype "passive"))
    )
    (net (code "77") (name "GND") (class "Default")
      (node (ref "C27") (pin "2") (pinfunction "2_2") (pintype "passive"))
      (node (ref "C28") (pin "2") (pinfunction "2_2") (pintype "passive"))
      (node (ref "C29") (pin "2") (pinfunction "2_2") (pintype "passive"))
      (node (ref "C30") (pin "2") (pinfunction "2_2") (pintype "passive"))
      (node (ref "C31") (pin "2") (pinfunction "2_2") (pintype "passive"))
      (node (ref "C33") (pin "1") (pinfunction "1_1") (pintype "passive"))
      (node (ref "C35") (pin "2") (pinfunction "2_2") (pintype "passive"))
      (node (ref "C36") (pin "2") (pinfunction "2_2") (pintype "passive"))
      (node (ref "C38") (pin "2") (pinfunction "2_2") (pintype "passive"))
      (node (ref "C39") (pin "1") (pinfunction "1_1") (pintype "passive"))
      (node (ref "C41") (pin "1") (pinfunction "1_1") (pintype "passive"))
      (node (ref "C42") (pin "2") (pinfunction "2_2") (pintype "passive"))
      (node (ref "C43") (pin "2") (pinfunction "2_2") (pintype "passive"))
      (node (ref "C45") (pin "2") (pinfunction "2_2") (pintype "passive"))
      (node (ref "C47") (pin "2") (pinfunction "2_2") (pintype "passive"))
      (node (ref "C48") (pin "2") (pinfunction "2_2") (pintype "passive"))
      (node (ref "C49") (pin "2") (pinfunction "2_2") (pintype "passive"))
      (node (ref "C9") (pin "1") (pinfunction "1_1") (pintype "passive"))
      (node (ref "D12") (pin "3") (pinfunction "C_3") (pintype "passive"))
      (node (ref "J1") (pin "1") (pinfunction "1_1") (pintype "passive"))
      (node (ref "J2") (pin "4") (pinfunction "4_4") (pintype "passive"))
      (node (ref "P5") (pin "1") (pinfunction "1_1") (pintype "passive"))
      (node (ref "P7") (pin "2") (pinfunction "2_2") (pintype "passive"))
      (node (ref "P9") (pin "2") (pinfunction "2_2") (pintype "passive"))
      (node (ref "Q10") (pin "2") (pinfunction "E_2") (pintype "passive"))
      (node (ref "Q5") (pin "2") (pinfunction "E_2") (pintype "passive"))
      (node (ref "Q8") (pin "2") (pinfunction "E_2") (pintype "passive"))
      (node (ref "R38") (pin "1") (pinfunction "1_1") (pintype "passive"))
      (node (ref "R78") (pin "2") (pinfunction "2_2") (pintype "passive"))
      (node (ref "S1") (pin "2") (pinfunction "2_2") (pintype "passive"))
      (node (ref "TP12") (pin "1") (pinfunction "1_1") (pintype "passive"))
      (node (ref "U10") (pin "4") (pinfunction "VSS_4") (pintype "passive"))
      (node (ref "U11") (pin "3") (pinfunction "GND_3") (pintype "passive"))
      (node (ref "U12") (pin "2") (pinfunction "GND_2") (pintype "passive"))
      (node (ref "U20") (pin "2") (pinfunction "GND_2") (pintype "passive"))
      (node (ref "U6") (pin "3") (pinfunction "GND_3") (pintype "passive"))
      (node (ref "U7") (pin "3") (pinfunction "GND_3") (pintype "passive"))
      (node (ref "U9") (pin "63") (pinfunction "VSS(VSSA)_63") (pintype "passive"))
      (node (ref "U9") (pin "65") (pinfunction "VREFN_65") (pintype "passive"))
    )
    (net (code "78") (name "Net-(B1-+)") (class "Default")
      (node (ref "B1") (pin "1") (pinfunction "+_1") (pintype "passive"))
      (node (ref "R42") (pin "1") (pinfunction "1_1") (pintype "passive"))
    )
    (net (code "79") (name "Net-(B1--)") (class "Default")
      (node (ref "B1") (pin "2") (pinfunction "-_2") (pintype "passive"))
      (node (ref "Q5") (pin "3") (pinfunction "C_3") (pintype "passive"))
    )
    (net (code "80") (name "Net-(D1-A)") (class "Default")
      (node (ref "D1") (pin "1") (pinfunction "A_1") (pintype "passive"))
      (node (ref "R17") (pin "1") (pinfunction "1_1") (pintype "passive"))
    )
    (net (code "81") (name "Net-(D1-K)") (class "Default")
      (node (ref "D1") (pin "2") (pinfunction "K_2") (pintype "passive"))
      (node (ref "Q10") (pin "3") (pinfunction "C_3") (pintype "passive"))
    )
    (net (code "82") (name "Net-(D7-Pad2)") (class "Default")
      (node (ref "D7") (pin "2") (pinfunction "2_2") (pintype "passive"))
      (node (ref "R7") (pin "2") (pinfunction "2_2") (pintype "passive"))
    )
    (net (code "83") (name "Net-(D11-A-Pad1)") (class "Default")
      (node (ref "D11") (pin "1") (pinfunction "A_1") (pintype "passive"))
      (node (ref "D11") (pin "2") (pinfunction "A_2") (pintype "passive"))
      (node (ref "R74") (pin "2") (pinfunction "2_2") (pintype "passive"))
    )
    (net (code "84") (name "Net-(D11-C)") (class "Default")
      (node (ref "D11") (pin "3") (pinfunction "C_3") (pintype "passive"))
      (node (ref "P5") (pin "2") (pinfunction "2_2") (pintype "passive"))
      (node (ref "TP20") (pin "1") (pinfunction "1_1") (pintype "passive"))
    )
    (net (code "85") (name "Net-(D12-A-Pad1)") (class "Default")
      (node (ref "D12") (pin "1") (pinfunction "A_1") (pintype "passive"))
      (node (ref "D12") (pin "2") (pinfunction "A_2") (pintype "passive"))
      (node (ref "R75") (pin "1") (pinfunction "1_1") (pintype "passive"))
    )
    (net (code "86") (name "Net-(J1-Pad2)") (class "Default")
      (node (ref "J1") (pin "2") (pinfunction "2_2") (pintype "passive"))
      (node (ref "R37") (pin "1") (pinfunction "1_1") (pintype "passive"))
    )
    (net (code "87") (name "Net-(J1-Pad3)") (class "Default")
      (node (ref "J1") (pin "3") (pinfunction "3_3") (pintype "passive"))
      (node (ref "R36") (pin "1") (pinfunction "1_1") (pintype "passive"))
    )
    (net (code "88") (name "Net-(J1-Pad4)") (class "Default")
      (node (ref "J1") (pin "4") (pinfunction "4_4") (pintype "passive"))
      (node (ref "R31") (pin "1") (pinfunction "1_1") (pintype "passive"))
    )
    (net (code "89") (name "Net-(J2-Pad1)") (class "Default")
      (node (ref "J2") (pin "1") (pinfunction "1_1") (pintype "passive"))
      (node (ref "R1") (pin "2") (pinfunction "2_2") (pintype "passive"))
    )
    (net (code "90") (name "Net-(Q5-B)") (class "Default")
      (node (ref "Q5") (pin "1") (pinfunction "B_1") (pintype "passive"))
      (node (ref "R47") (pin "2") (pinfunction "2_2") (pintype "passive"))
    )
    (net (code "91") (name "Net-(Q7-B)") (class "Default")
      (node (ref "Q7") (pin "1") (pinfunction "B_1") (pintype "passive"))
      (node (ref "R27") (pin "2") (pinfunction "2_2") (pintype "passive"))
    )
    (net (code "92") (name "Net-(Q8-B)") (class "Default")
      (node (ref "Q8") (pin "1") (pinfunction "B_1") (pintype "passive"))
      (node (ref "R31") (pin "2") (pinfunction "2_2") (pintype "passive"))
      (node (ref "R38") (pin "2") (pinfunction "2_2") (pintype "passive"))
    )
    (net (code "93") (name "Net-(Q9-B)") (class "Default")
      (node (ref "Q9") (pin "1") (pinfunction "B_1") (pintype "passive"))
      (node (ref "R10") (pin "1") (pinfunction "1_1") (pintype "passive"))
      (node (ref "R12") (pin "2") (pinfunction "2_2") (pintype "passive"))
    )
    (net (code "94") (name "Net-(Q9-C)") (class "Default")
      (node (ref "Q9") (pin "3") (pinfunction "C_3") (pintype "passive"))
      (node (ref "R17") (pin "2") (pinfunction "2_2") (pintype "passive"))
    )
    (net (code "95") (name "Net-(Q10-B)") (class "Default")
      (node (ref "Q10") (pin "1") (pinfunction "B_1") (pintype "passive"))
      (node (ref "R20") (pin "2") (pinfunction "2_2") (pintype "passive"))
    )
    (net (code "96") (name "Net-(Q11-B)") (class "Default")
      (node (ref "Q11") (pin "1") (pinfunction "B_1") (pintype "passive"))
      (node (ref "R3") (pin "2") (pinfunction "2_2") (pintype "passive"))
    )
    (net (code "97") (name "Net-(Q12-B)") (class "Default")
      (node (ref "Q12") (pin "1") (pinfunction "B_1") (pintype "passive"))
      (node (ref "R49") (pin "2") (pinfunction "2_2") (pintype "passive"))
    )
    (net (code "98") (name "Net-(Q12-C)") (class "Default")
      (node (ref "C36") (pin "1") (pinfunction "1_1") (pintype "passive"))
      (node (ref "Q12") (pin "3") (pinfunction "C_3") (pintype "passive"))
      (node (ref "U10") (pin "3") (pinfunction "WP#_3") (pintype "passive"))
      (node (ref "U10") (pin "7") (pinfunction "HOLD#_7") (pintype "passive"))
      (node (ref "U10") (pin "8") (pinfunction "VDD_8") (pintype "passive"))
    )
    (net (code "99") (name "Net-(Q13-B)") (class "Default")
      (node (ref "Q13") (pin "1") (pinfunction "B_1") (pintype "passive"))
      (node (ref "R74") (pin "1") (pinfunction "1_1") (pintype "passive"))
      (node (ref "R76") (pin "2") (pinfunction "2_2") (pintype "passive"))
    )
    (net (code "100") (name "Net-(U9-VDD15)") (class "Default")
      (node (ref "C38") (pin "1") (pinfunction "1_1") (pintype "passive"))
      (node (ref "U9") (pin "62") (pinfunction "VDD15_62") (pintype "passive"))
    )
    (net (code "101") (name "Net-(U12-OUT)") (class "Default")
      (node (ref "R9") (pin "1") (pinfunction "1_1") (pintype "passive"))
      (node (ref "U12") (pin "1") (pinfunction "OUT_1") (pintype "passive"))
    )
    (net (code "102") (name "Net-(U20-SDO)") (class "Default")
      (node (ref "R78") (pin "1") (pinfunction "1_1") (pintype "passive"))
      (node (ref "R79") (pin "1") (pinfunction "1_1") (pintype "passive"))
      (node (ref "U20") (pin "8") (pinfunction "SDO_8") (pintype "passive"))
    )
    (net (code "103") (name "unconnected-(U9-PE8-Pad20)") (class "Default")
      (node (ref "U9") (pin "20") (pinfunction "PE8_20") (pintype "passive"))
    )
    (net (code "104") (name "unconnected-(U20-CSB-Pad7)") (class "Default")
      (node (ref "U20") (pin "7") (pinfunction "CSB_7") (pintype "passive"))
    )
    (net (code "105") (name "unconnected-(U20-NC-Pad4)") (class "Default")
      (node (ref "U20") (pin "4") (pinfunction "NC_4") (pintype "passive+no_connect"))
    )
  )
)
